# 4_20ma.net
KiCad netlist of a schematic drawn in Altium Designer
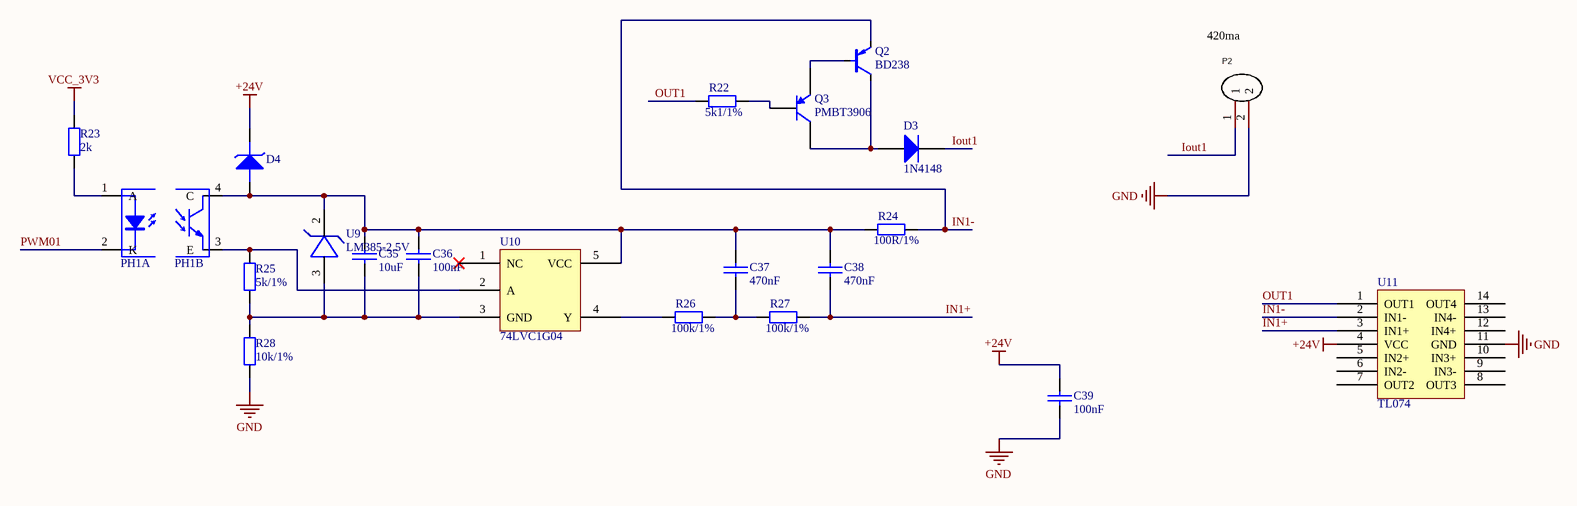
[diagram p0: 4~20ma.SchDoc]

(export (version "E")
  (design (tool "Eeschema 10.0.6"))
  (components
    (comp (ref "C35")
      (value "10uF")
      (footprint "C-0805")
      (description "电容")
      (libsource (lib "泰开常用器件") (part "C普通电容"))
    )
    (comp (ref "C36")
      (value "100nF")
      (footprint "C-0805")
      (description "电容")
      (libsource (lib "泰开常用器件") (part "C普通电容"))
    )
    (comp (ref "C37")
      (value "470nF")
      (footprint "C-0805")
      (description "电容")
      (libsource (lib "泰开常用器件") (part "C普通电容"))
    )
    (comp (ref "C38")
      (value "470nF")
      (footprint "C-0805")
      (description "电容")
      (libsource (lib "泰开常用器件") (part "C普通电容"))
    )
    (comp (ref "C39")
      (value "100nF")
      (footprint "C-0805")
      (description "电容")
      (libsource (lib "泰开常用器件") (part "C普通电容"))
    )
    (comp (ref "D3")
      (value "1N4148")
      (footprint "LL-34")
      (description "1 Amp General Purpose Rectifier")
      (fields (field (name "PUBLISHER") "Altium Limited"))
      (libsource (lib "泰开常用器件") (part "D二极管"))
    )
    (comp (ref "D4")
      (value "1N4732")
      (footprint "DO-214AC")
      (description "稳压二极管")
      (libsource (lib "泰开常用器件(3)") (part "D稳压二极管"))
    )
    (comp (ref "P2")
      (value "WJ500V-5.08-2P")
      (footprint "KF128-2P DG128")
      (fields (field (name "MANUFACTURER") "KANGNEX(康奈克斯电气)"))
      (libsource (lib "泰开常用器件") (part "WJ500V-5.08-2P"))
    )
    (comp (ref "PH1")
      (value "PCA817")
      (footprint "SMD-4_L6.5-W4.6-P2.54-LS10.3-TL")
      (libsource (lib "泰开常用器件") (part "PHOTOCOUPL SEP"))
    )
    (comp (ref "Q2")
      (value "BD238")
      (footprint "TO-126")
      (description "三极管")
      (libsource (lib "常用器件") (part "PNP"))
    )
    (comp (ref "Q3") (value "PMBT3906") (footprint "SOT-23-3") (libsource (lib "泰开常用器件") (part "PNP")))
    (comp (ref "R22")
      (value "5k1/1%")
      (footprint "R-0805")
      (description "电阻")
      (fields (field (name "PUBLISHER") "Altium Limited"))
      (libsource (lib "泰开常用器件") (part "RES"))
    )
    (comp (ref "R23")
      (value "2k")
      (footprint "R-0805")
      (description "电阻")
      (fields (field (name "PUBLISHER") "Altium Limited"))
      (libsource (lib "") (part "RES_1"))
    )
    (comp (ref "R24")
      (value "100R/1%")
      (footprint "R-0805")
      (description "电阻")
      (fields (field (name "PUBLISHER") "Altium Limited"))
      (libsource (lib "泰开常用器件") (part "RES"))
    )
    (comp (ref "R25")
      (value "5k/1%")
      (footprint "R-0805")
      (description "电阻")
      (fields (field (name "PUBLISHER") "Altium Limited"))
      (libsource (lib "") (part "RES_1"))
    )
    (comp (ref "R26")
      (value "100k/1%")
      (footprint "R-0805")
      (description "电阻")
      (fields (field (name "PUBLISHER") "Altium Limited"))
      (libsource (lib "泰开常用器件") (part "RES"))
    )
    (comp (ref "R27")
      (value "100k/1%")
      (footprint "R-0805")
      (description "电阻")
      (fields (field (name "PUBLISHER") "Altium Limited"))
      (libsource (lib "泰开常用器件") (part "RES"))
    )
    (comp (ref "R28")
      (value "10k/1%")
      (footprint "R-0805")
      (description "电阻")
      (fields (field (name "PUBLISHER") "Altium Limited"))
      (libsource (lib "") (part "RES_1"))
    )
    (comp (ref "U9") (value "LM385-2.5V") (footprint "TO-92") (libsource (lib "泰开常用器件") (part "LM358-2.5V")))
    (comp (ref "U10")
      (value "74LVC1G04")
      (footprint "SOT-23-5")
      (libsource (lib "泰开常用器件") (part "74LVC1G04"))
    )
    (comp (ref "U11") (value "TL074") (footprint "SO-14") (libsource (lib "芯片") (part "TL074")))
  )
  (nets
    (net (code "1") (name "+24V") (class "Default")
      (node (ref "C39") (pin "2") (pinfunction "2_2") (pintype "passive"))
      (node (ref "D4") (pin "2") (pinfunction "K_2") (pintype "passive"))
      (node (ref "U11") (pin "4") (pinfunction "VCC_4") (pintype "passive"))
    )
    (net (code "2") (name "/IN1+") (class "Default")
      (node (ref "C38") (pin "1") (pinfunction "1_1") (pintype "passive"))
      (node (ref "R27") (pin "1") (pinfunction "1_1") (pintype "passive"))
      (node (ref "U11") (pin "3") (pinfunction "IN1+_3") (pintype "passive"))
    )
    (net (code "3") (name "/IN1-") (class "Default")
      (node (ref "Q2") (pin "1") (pinfunction "e_1") (pintype "passive"))
      (node (ref "R24") (pin "1") (pinfunction "1_1") (pintype "passive"))
      (node (ref "U11") (pin "2") (pinfunction "IN1-_2") (pintype "passive"))
    )
    (net (code "4") (name "/Iout1") (class "Default")
      (node (ref "D3") (pin "2") (pinfunction "K_2") (pintype "passive"))
      (node (ref "P2") (pin "1") (pinfunction "1_1") (pintype "passive"))
    )
    (net (code "5") (name "/OUT1") (class "Default")
      (node (ref "R22") (pin "2") (pinfunction "2_2") (pintype "passive"))
      (node (ref "U11") (pin "1") (pinfunction "OUT1_1") (pintype "passive"))
    )
    (net (code "6") (name "/PWM01") (class "Default")
      (node (ref "PH1") (pin "2") (pinfunction "K_2") (pintype "passive"))
    )
    (net (code "7") (name "GND") (class "Default")
      (node (ref "C39") (pin "1") (pinfunction "1_1") (pintype "passive"))
      (node (ref "P2") (pin "2") (pinfunction "2_2") (pintype "passive"))
      (node (ref "R28") (pin "2") (pinfunction "2_2") (pintype "passive"))
      (node (ref "U11") (pin "11") (pinfunction "GND_11") (pintype "passive"))
    )
    (net (code "8") (name "Net-(C37-Pad1)") (class "Default")
      (node (ref "C37") (pin "1") (pinfunction "1_1") (pintype "passive"))
      (node (ref "R26") (pin "1") (pinfunction "1_1") (pintype "passive"))
      (node (ref "R27") (pin "2") (pinfunction "2_2") (pintype "passive"))
    )
    (net (code "9") (name "Net-(D3-A)") (class "Default")
      (node (ref "D3") (pin "1") (pinfunction "A_1") (pintype "passive"))
      (node (ref "Q2") (pin "2") (pinfunction "c_2") (pintype "passive"))
      (node (ref "Q3") (pin "3") (pinfunction "C_3") (pintype "passive"))
    )
    (net (code "10") (name "Net-(D4-A)") (class "Default")
      (node (ref "C35") (pin "1") (pinfunction "1_1") (pintype "passive"))
      (node (ref "C36") (pin "2") (pinfunction "2_2") (pintype "passive"))
      (node (ref "C37") (pin "2") (pinfunction "2_2") (pintype "passive"))
      (node (ref "C38") (pin "2") (pinfunction "2_2") (pintype "passive"))
      (node (ref "D4") (pin "1") (pinfunction "A_1") (pintype "passive"))
      (node (ref "PH1") (pin "4") (pinfunction "C_4") (pintype "passive"))
      (node (ref "R24") (pin "2") (pinfunction "2_2") (pintype "passive"))
      (node (ref "U10") (pin "5") (pinfunction "VCC_5") (pintype "passive"))
      (node (ref "U9") (pin "2") (pinfunction "C_2") (pintype "passive"))
    )
    (net (code "11") (name "Net-(PH1A-A)") (class "Default")
      (node (ref "PH1") (pin "1") (pinfunction "A_1") (pintype "passive"))
      (node (ref "R23") (pin "2") (pinfunction "2_2") (pintype "passive"))
    )
    (net (code "12") (name "Net-(PH1B-E)") (class "Default")
      (node (ref "PH1") (pin "3") (pinfunction "E_3") (pintype "passive"))
      (node (ref "R25") (pin "1") (pinfunction "1_1") (pintype "passive"))
      (node (ref "U10") (pin "2") (pinfunction "A_2") (pintype "passive"))
    )
    (net (code "13") (name "Net-(Q2-b)") (class "Default")
      (node (ref "Q2") (pin "3") (pinfunction "b_3") (pintype "passive"))
      (node (ref "Q3") (pin "2") (pinfunction "E_2") (pintype "passive"))
    )
    (net (code "14") (name "Net-(Q3-B)") (class "Default")
      (node (ref "Q3") (pin "1") (pinfunction "B_1") (pintype "passive"))
      (node (ref "R22") (pin "1") (pinfunction "1_1") (pintype "passive"))
    )
    (net (code "15") (name "Net-(U10-GND)") (class "Default")
      (node (ref "C35") (pin "2") (pinfunction "2_2") (pintype "passive"))
      (node (ref "C36") (pin "1") (pinfunction "1_1") (pintype "passive"))
      (node (ref "R25") (pin "2") (pinfunction "2_2") (pintype "passive"))
      (node (ref "R28") (pin "1") (pinfunction "1_1") (pintype "passive"))
      (node (ref "U10") (pin "3") (pinfunction "GND_3") (pintype "passive"))
      (node (ref "U9") (pin "3") (pinfunction "A_3") (pintype "passive"))
    )
    (net (code "16") (name "Net-(U10-Y)") (class "Default")
      (node (ref "R26") (pin "2") (pinfunction "2_2") (pintype "passive"))
      (node (ref "U10") (pin "4") (pinfunction "Y_4") (pintype "passive"))
    )
    (net (code "17") (name "VCC_3V3") (class "Default")
      (node (ref "R23") (pin "1") (pinfunction "1_1") (pintype "passive"))
    )
    (net (code "18") (name "unconnected-(U10-NC-Pad1)") (class "Default")
      (node (ref "U10") (pin "1") (pinfunction "NC_1") (pintype "passive+no_connect"))
    )
    (net (code "19") (name "unconnected-(U11-IN2+-Pad5)") (class "Default")
      (node (ref "U11") (pin "5") (pinfunction "IN2+_5") (pintype "passive"))
    )
    (net (code "20") (name "unconnected-(U11-IN2--Pad6)") (class "Default")
      (node (ref "U11") (pin "6") (pinfunction "IN2-_6") (pintype "passive"))
    )
    (net (code "21") (name "unconnected-(U11-IN3+-Pad10)") (class "Default")
      (node (ref "U11") (pin "10") (pinfunction "IN3+_10") (pintype "passive"))
    )
    (net (code "22") (name "unconnected-(U11-IN3--Pad9)") (class "Default")
      (node (ref "U11") (pin "9") (pinfunction "IN3-_9") (pintype "passive"))
    )
    (net (code "23") (name "unconnected-(U11-IN4+-Pad12)") (class "Default")
      (node (ref "U11") (pin "12") (pinfunction "IN4+_12") (pintype "passive"))
    )
    (net (code "24") (name "unconnected-(U11-IN4--Pad13)") (class "Default")
      (node (ref "U11") (pin "13") (pinfunction "IN4-_13") (pintype "passive"))
    )
    (net (code "25") (name "unconnected-(U11-OUT2-Pad7)") (class "Default")
      (node (ref "U11") (pin "7") (pinfunction "OUT2_7") (pintype "passive"))
    )
    (net (code "26") (name "unconnected-(U11-OUT3-Pad8)") (class "Default")
      (node (ref "U11") (pin "8") (pinfunction "OUT3_8") (pintype "passive"))
    )
    (net (code "27") (name "unconnected-(U11-OUT4-Pad14)") (class "Default")
      (node (ref "U11") (pin "14") (pinfunction "OUT4_14") (pintype "passive"))
    )
  )
)
